# speaker_amp_single.net
KiCad netlist of a schematic drawn in EAGLE
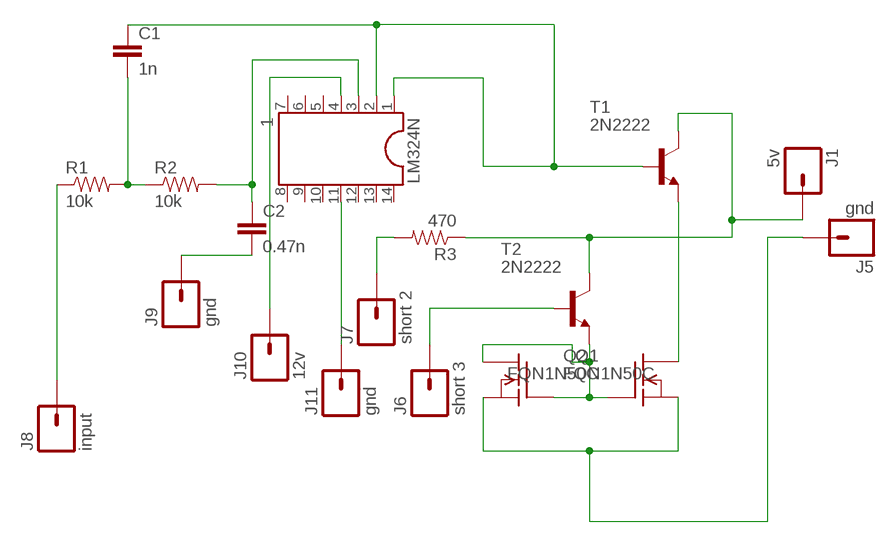
[diagram p0: schematic, sheet 1]

(export (version "E")
  (design (tool "Eeschema 10.0.6"))
  (components
    (comp (ref "C1")
      (value "1n")
      (footprint "eagle-import:CAP-PTH-SMALL")
      (libsource (lib "eagle-import") (part "CAPPTH"))
    )
    (comp (ref "C2")
      (value "0.47n")
      (footprint "eagle-import:CAP-PTH-SMALL")
      (libsource (lib "eagle-import") (part "CAPPTH"))
    )
    (comp (ref "J1")
      (value "5v")
      (footprint "eagle-import:1X01")
      (libsource (lib "eagle-import") (part "M01PTH"))
    )
    (comp (ref "J5")
      (value "gnd")
      (footprint "eagle-import:1X01")
      (libsource (lib "eagle-import") (part "M01PTH"))
    )
    (comp (ref "J6")
      (value "short 3")
      (footprint "eagle-import:1X01")
      (libsource (lib "eagle-import") (part "M01PTH"))
    )
    (comp (ref "J7")
      (value "short 2")
      (footprint "eagle-import:1X01")
      (libsource (lib "eagle-import") (part "M01PTH"))
    )
    (comp (ref "J8")
      (value "input")
      (footprint "eagle-import:1X01")
      (libsource (lib "eagle-import") (part "M01PTH"))
    )
    (comp (ref "J9")
      (value "gnd")
      (footprint "eagle-import:1X01")
      (libsource (lib "eagle-import") (part "M01PTH"))
    )
    (comp (ref "J10")
      (value "12v")
      (footprint "eagle-import:1X01")
      (libsource (lib "eagle-import") (part "M01PTH"))
    )
    (comp (ref "J11")
      (value "gnd")
      (footprint "eagle-import:1X01")
      (libsource (lib "eagle-import") (part "M01PTH"))
    )
    (comp (ref "LM324N")
      (value "1")
      (footprint "eagle-import:DIL14")
      (libsource (lib "eagle-import") (part "DIL14"))
    )
    (comp (ref "Q1")
      (value "FQN1N50C")
      (footprint "eagle-import:TO92")
      (libsource (lib "eagle-import") (part "FQN1N50C"))
    )
    (comp (ref "Q2")
      (value "FQN1N50C")
      (footprint "eagle-import:TO92")
      (libsource (lib "eagle-import") (part "FQN1N50C"))
    )
    (comp (ref "R1")
      (value "10k")
      (footprint "eagle-import:AXIAL-0.3")
      (libsource (lib "eagle-import") (part "RESISTORAXIAL-0.3"))
    )
    (comp (ref "R2")
      (value "10k")
      (footprint "eagle-import:AXIAL-0.3")
      (libsource (lib "eagle-import") (part "RESISTORAXIAL-0.3"))
    )
    (comp (ref "R3")
      (value "470")
      (footprint "eagle-import:AXIAL-0.3")
      (libsource (lib "eagle-import") (part "RESISTORAXIAL-0.3"))
    )
    (comp (ref "T1")
      (value "2N2222")
      (footprint "eagle-import:TO92-EBC-OVAL")
      (libsource (lib "eagle-import") (part "2N2222"))
    )
    (comp (ref "T2")
      (value "2N2222")
      (footprint "eagle-import:TO92-EBC-OVAL")
      (libsource (lib "eagle-import") (part "2N2222"))
    )
  )
  (nets
    (net (code "1") (name "Net-(C1-Pad1)") (class "Default")
      (node (ref "C1") (pin "1") (pinfunction "1_1") (pintype "passive"))
      (node (ref "LM324N") (pin "1") (pinfunction "1_1") (pintype "passive"))
      (node (ref "LM324N") (pin "2") (pinfunction "2_2") (pintype "passive"))
      (node (ref "T1") (pin "B") (pinfunction "B_B") (pintype "passive"))
    )
    (net (code "2") (name "Net-(C2-Pad2)") (class "Default")
      (node (ref "C2") (pin "2") (pinfunction "2_2") (pintype "passive"))
      (node (ref "J9") (pin "1") (pinfunction "1_1") (pintype "passive"))
    )
    (net (code "3") (name "Net-(J6-Pad1)") (class "Default")
      (node (ref "J6") (pin "1") (pinfunction "1_1") (pintype "passive"))
      (node (ref "T2") (pin "B") (pinfunction "B_B") (pintype "passive"))
    )
    (net (code "4") (name "Net-(J10-Pad1)") (class "Default")
      (node (ref "J10") (pin "1") (pinfunction "1_1") (pintype "passive"))
      (node (ref "LM324N") (pin "4") (pinfunction "4_4") (pintype "passive"))
    )
    (net (code "5") (name "Net-(J11-Pad1)") (class "Default")
      (node (ref "J11") (pin "1") (pinfunction "1_1") (pintype "passive"))
      (node (ref "LM324N") (pin "11") (pinfunction "11_11") (pintype "passive"))
    )
    (net (code "6") (name "Net-(Q1-D)") (class "Default")
      (node (ref "Q1") (pin "1") (pinfunction "G_1") (pintype "passive"))
      (node (ref "Q1") (pin "2") (pinfunction "D_2") (pintype "passive"))
      (node (ref "Q2") (pin "1") (pinfunction "G_1") (pintype "passive"))
      (node (ref "T2") (pin "E") (pinfunction "E_E") (pintype "passive"))
    )
    (net (code "7") (name "Net-(Q1-S)") (class "Default")
      (node (ref "J5") (pin "1") (pinfunction "1_1") (pintype "passive"))
      (node (ref "Q1") (pin "3") (pinfunction "S_3") (pintype "passive"))
      (node (ref "Q2") (pin "3") (pinfunction "S_3") (pintype "passive"))
    )
    (net (code "8") (name "Net-(Q2-D)") (class "Default")
      (node (ref "Q2") (pin "2") (pinfunction "D_2") (pintype "passive"))
      (node (ref "T1") (pin "E") (pinfunction "E_E") (pintype "passive"))
    )
    (net (code "9") (name "Net-(R1-1)") (class "Default")
      (node (ref "J8") (pin "1") (pinfunction "1_1") (pintype "passive"))
      (node (ref "R1") (pin "P$1") (pinfunction "1_P$1") (pintype "passive"))
    )
    (net (code "10") (name "Net-(R1-2)") (class "Default")
      (node (ref "C1") (pin "2") (pinfunction "2_2") (pintype "passive"))
      (node (ref "R1") (pin "P$2") (pinfunction "2_P$2") (pintype "passive"))
      (node (ref "R2") (pin "P$1") (pinfunction "1_P$1") (pintype "passive"))
    )
    (net (code "11") (name "Net-(R2-2)") (class "Default")
      (node (ref "C2") (pin "1") (pinfunction "1_1") (pintype "passive"))
      (node (ref "LM324N") (pin "3") (pinfunction "3_3") (pintype "passive"))
      (node (ref "R2") (pin "P$2") (pinfunction "2_P$2") (pintype "passive"))
    )
    (net (code "12") (name "Net-(R3-1)") (class "Default")
      (node (ref "J1") (pin "1") (pinfunction "1_1") (pintype "passive"))
      (node (ref "R3") (pin "P$1") (pinfunction "1_P$1") (pintype "passive"))
      (node (ref "T1") (pin "C") (pinfunction "C_C") (pintype "passive"))
      (node (ref "T2") (pin "C") (pinfunction "C_C") (pintype "passive"))
    )
    (net (code "13") (name "Net-(R3-2)") (class "Default")
      (node (ref "J7") (pin "1") (pinfunction "1_1") (pintype "passive"))
      (node (ref "R3") (pin "P$2") (pinfunction "2_P$2") (pintype "passive"))
    )
    (net (code "14") (name "unconnected-(LM324N-Pad5)") (class "Default")
      (node (ref "LM324N") (pin "5") (pinfunction "5_5") (pintype "passive"))
    )
    (net (code "15") (name "unconnected-(LM324N-Pad6)") (class "Default")
      (node (ref "LM324N") (pin "6") (pinfunction "6_6") (pintype "passive"))
    )
    (net (code "16") (name "unconnected-(LM324N-Pad7)") (class "Default")
      (node (ref "LM324N") (pin "7") (pinfunction "7_7") (pintype "passive"))
    )
    (net (code "17") (name "unconnected-(LM324N-Pad8)") (class "Default")
      (node (ref "LM324N") (pin "8") (pinfunction "8_8") (pintype "passive"))
    )
    (net (code "18") (name "unconnected-(LM324N-Pad9)") (class "Default")
      (node (ref "LM324N") (pin "9") (pinfunction "9_9") (pintype "passive"))
    )
    (net (code "19") (name "unconnected-(LM324N-Pad10)") (class "Default")
      (node (ref "LM324N") (pin "10") (pinfunction "10_10") (pintype "passive"))
    )
    (net (code "20") (name "unconnected-(LM324N-Pad12)") (class "Default")
      (node (ref "LM324N") (pin "12") (pinfunction "12_12") (pintype "passive"))
    )
    (net (code "21") (name "unconnected-(LM324N-Pad13)") (class "Default")
      (node (ref "LM324N") (pin "13") (pinfunction "13_13") (pintype "passive"))
    )
    (net (code "22") (name "unconnected-(LM324N-Pad14)") (class "Default")
      (node (ref "LM324N") (pin "14") (pinfunction "14_14") (pintype "passive"))
    )
  )
)
